# SFPGA.net
KiCad netlist of a schematic drawn in Altium Designer
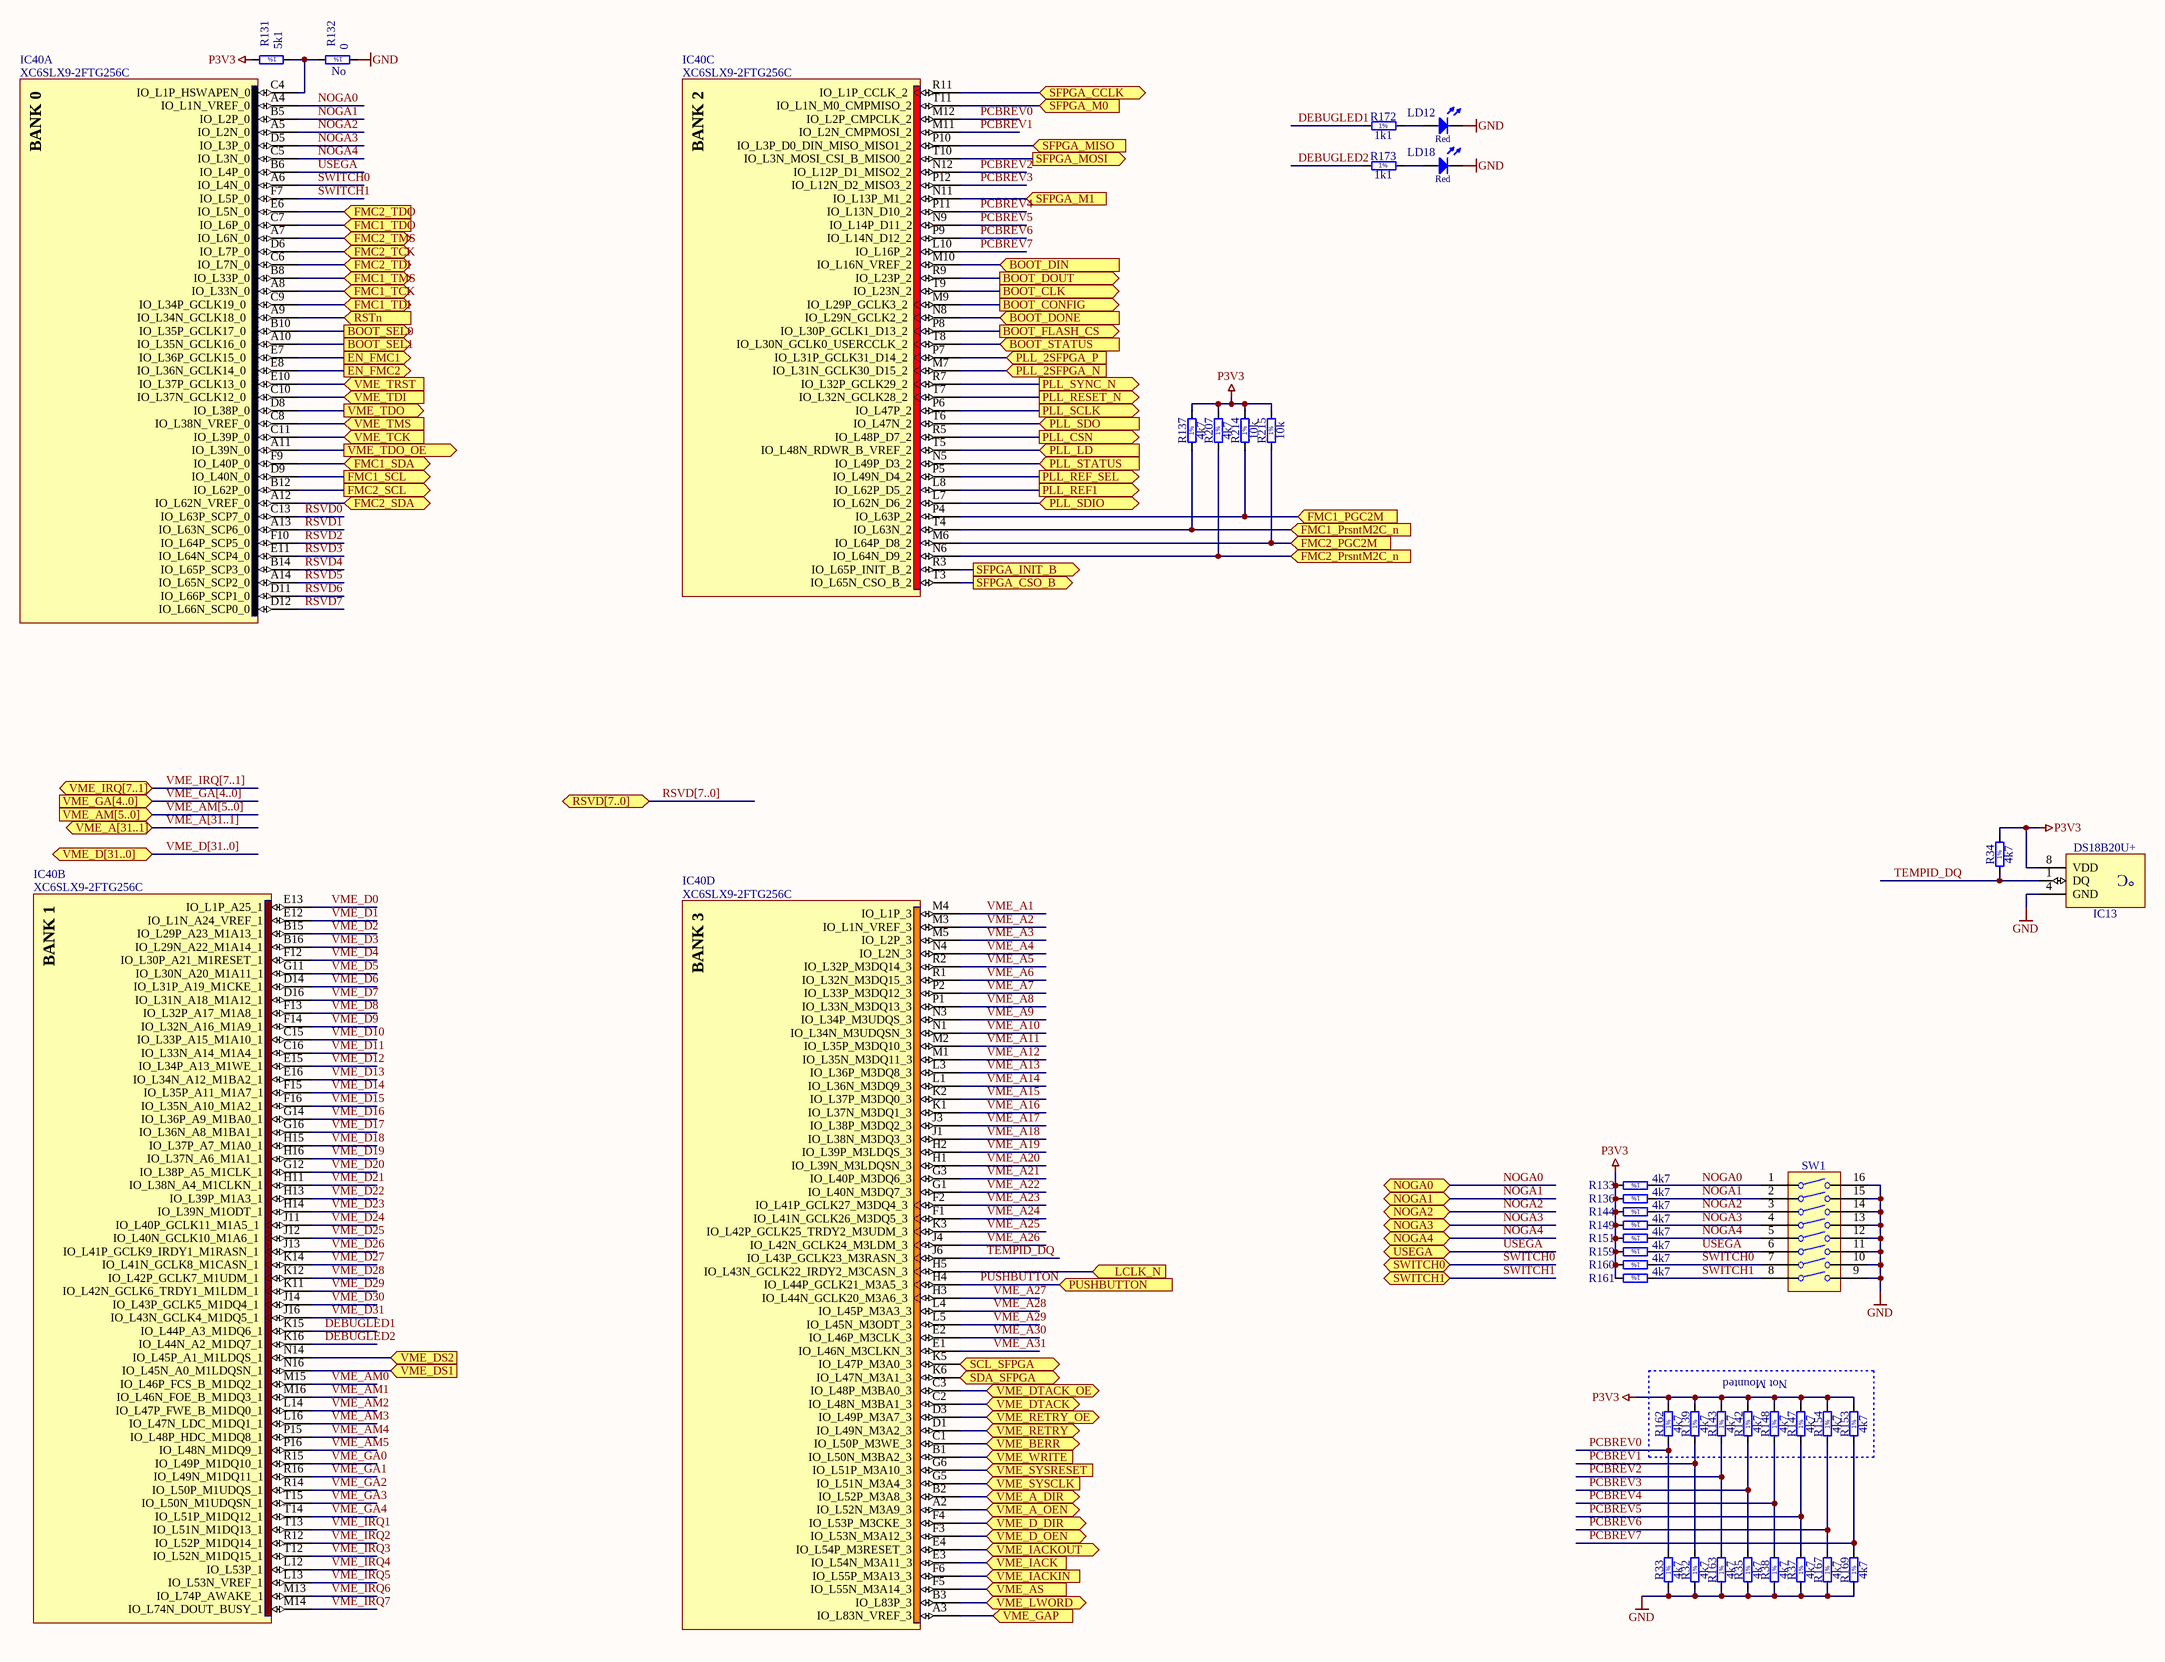
[diagram p0: SFPGA.SchDoc]

(export (version "E")
  (design (tool "Eeschema 10.0.6"))
  (components
    (comp (ref "IC13")
      (value "DS18B20U+")
      (footprint "SOP65P490X110-8N")
      (description "Programmable Resolution 1-Wire Digital Thermometer")
      (fields (field (name "MANUFACTURER") "DALLAS MAXIM") (field (name "AUTHOR") "CERN DEM JLC"))
      (libsource (lib "ICs And Semiconductors") (part "DS18B20U+"))
    )
    (comp (ref "IC40")
      (value "XC6SLX9-2FTG256C")
      (footprint "BGA256C100P16X16_1700X1700X155")
      (fields (field (name "MANUFACTURER") "XILINX") (field (name "AUTHOR") "CERN DEM JLC"))
      (libsource (lib "ICs And Semiconductors") (part "XC6SLX9-2FTG256C"))
    )
    (comp (ref "LD12")
      (value "Red")
      (footprint "LEDC1608X80N_RED")
      (description "LED Red 1C 2A")
      (fields
        (field (name "PART NUMBER") "LED_ROHM_SML-311UTT86K")
        (field (name "MANUFACTURER") "ROHM")
        (field (name "AUTHOR") "CERN DEM JLC")
      )
      (libsource (lib "ICs And Semiconductors") (part "LED Red 1C 2A"))
    )
    (comp (ref "LD18")
      (value "Red")
      (footprint "LEDC1608X80N_RED")
      (description "LED Red 1C 2A")
      (fields
        (field (name "PART NUMBER") "LED_ROHM_SML-311UTT86K")
        (field (name "MANUFACTURER") "ROHM")
        (field (name "AUTHOR") "CERN DEM JLC")
      )
      (libsource (lib "ICs And Semiconductors") (part "LED Red 1C 2A"))
    )
    (comp (ref "R32")
      (value "4k7")
      (footprint "RESC1608X55N")
      (description "Resistor - 1%")
      (fields
        (field (name "PART NUMBER") "R0603_4K7_1%_0.1W_100PPM")
        (field (name "POWER") "0.1W")
        (field (name "AUTHOR") "CERN DEM JLC")
      )
      (libsource (lib "Resistors") (part "Resistor - 1%"))
    )
    (comp (ref "R33")
      (value "4k7")
      (footprint "RESC1608X55N")
      (description "Resistor - 1%")
      (fields
        (field (name "PART NUMBER") "R0603_4K7_1%_0.1W_100PPM")
        (field (name "POWER") "0.1W")
        (field (name "AUTHOR") "CERN DEM JLC")
      )
      (libsource (lib "Resistors") (part "Resistor - 1%"))
    )
    (comp (ref "R34")
      (value "4k7")
      (footprint "RESC1608X55N")
      (description "Resistor - 1%")
      (fields
        (field (name "PART NUMBER") "R0603_4K7_1%_0.1W_100PPM")
        (field (name "POWER") "0.1W")
        (field (name "AUTHOR") "CERN DEM JLC")
      )
      (libsource (lib "Resistors") (part "Resistor - 1%"))
    )
    (comp (ref "R35")
      (value "4k7")
      (footprint "RESC1608X55N")
      (description "Resistor - 1%")
      (fields
        (field (name "PART NUMBER") "R0603_4K7_1%_0.1W_100PPM")
        (field (name "POWER") "0.1W")
        (field (name "AUTHOR") "CERN DEM JLC")
      )
      (libsource (lib "Resistors") (part "Resistor - 1%"))
    )
    (comp (ref "R37")
      (value "4k7")
      (footprint "RESC1608X55N")
      (description "Resistor - 1%")
      (fields
        (field (name "PART NUMBER") "R0603_4K7_1%_0.1W_100PPM")
        (field (name "POWER") "0.1W")
        (field (name "AUTHOR") "CERN DEM JLC")
      )
      (libsource (lib "Resistors") (part "Resistor - 1%"))
    )
    (comp (ref "R38")
      (value "4k7")
      (footprint "RESC1608X55N")
      (description "Resistor - 1%")
      (fields
        (field (name "PART NUMBER") "R0603_4K7_1%_0.1W_100PPM")
        (field (name "POWER") "0.1W")
        (field (name "AUTHOR") "CERN DEM JLC")
      )
      (libsource (lib "Resistors") (part "Resistor - 1%"))
    )
    (comp (ref "R131")
      (value "5k1")
      (footprint "RESC1608X55N")
      (description "Resistor - 1%")
      (fields
        (field (name "PART NUMBER") "R0603_5K1_1%_0.1W_100PPM")
        (field (name "POWER") "0.1W")
        (field (name "AUTHOR") "CERN DEM JLC")
      )
      (libsource (lib "Resistors") (part "Resistor - 1%"))
    )
    (comp (ref "R132")
      (value "0")
      (footprint "RESC1608X55N")
      (description "Resistor - 1%")
      (fields
        (field (name "PART NUMBER") "R0603_0R_JUMPER")
        (field (name "MANUFACTURER") "GENERIC")
        (field (name "MOUNTED") "No")
        (field (name "AUTHOR") "CERN DEM JLC")
      )
      (libsource (lib "Resistors") (part "Resistor - 1%"))
    )
    (comp (ref "R133")
      (value "4k7")
      (footprint "RESC1608X55N")
      (description "Resistor - 1%")
      (fields
        (field (name "PART NUMBER") "R0603_4K7_1%_0.1W_100PPM")
        (field (name "POWER") "0.1W")
        (field (name "AUTHOR") "CERN DEM JLC")
      )
      (libsource (lib "Resistors") (part "Resistor - 1%"))
    )
    (comp (ref "R136")
      (value "4k7")
      (footprint "RESC1608X55N")
      (description "Resistor - 1%")
      (fields
        (field (name "PART NUMBER") "R0603_4K7_1%_0.1W_100PPM")
        (field (name "POWER") "0.1W")
        (field (name "AUTHOR") "CERN DEM JLC")
      )
      (libsource (lib "Resistors") (part "Resistor - 1%"))
    )
    (comp (ref "R137")
      (value "4k7")
      (footprint "RESC1608X55N")
      (description "Resistor - 1%")
      (fields
        (field (name "PART NUMBER") "R0603_4K7_1%_0.1W_100PPM")
        (field (name "POWER") "0.1W")
        (field (name "AUTHOR") "CERN DEM JLC")
      )
      (libsource (lib "Resistors") (part "Resistor - 1%"))
    )
    (comp (ref "R139")
      (value "4k7")
      (footprint "RESC1608X55N")
      (description "Resistor - 1%")
      (fields
        (field (name "PART NUMBER") "R0603_4K7_1%_0.1W_100PPM")
        (field (name "POWER") "0.1W")
        (field (name "AUTHOR") "CERN DEM JLC")
      )
      (libsource (lib "Resistors") (part "Resistor - 1%"))
    )
    (comp (ref "R142")
      (value "4k7")
      (footprint "RESC1608X55N")
      (description "Resistor - 1%")
      (fields
        (field (name "PART NUMBER") "R0603_4K7_1%_0.1W_100PPM")
        (field (name "POWER") "0.1W")
        (field (name "AUTHOR") "CERN DEM JLC")
      )
      (libsource (lib "Resistors") (part "Resistor - 1%"))
    )
    (comp (ref "R143")
      (value "4k7")
      (footprint "RESC1608X55N")
      (description "Resistor - 1%")
      (fields
        (field (name "PART NUMBER") "R0603_4K7_1%_0.1W_100PPM")
        (field (name "POWER") "0.1W")
        (field (name "AUTHOR") "CERN DEM JLC")
      )
      (libsource (lib "Resistors") (part "Resistor - 1%"))
    )
    (comp (ref "R144")
      (value "4k7")
      (footprint "RESC1608X55N")
      (description "Resistor - 1%")
      (fields
        (field (name "PART NUMBER") "R0603_4K7_1%_0.1W_100PPM")
        (field (name "POWER") "0.1W")
        (field (name "AUTHOR") "CERN DEM JLC")
      )
      (libsource (lib "Resistors") (part "Resistor - 1%"))
    )
    (comp (ref "R147")
      (value "4k7")
      (footprint "RESC1608X55N")
      (description "Resistor - 1%")
      (fields
        (field (name "PART NUMBER") "R0603_4K7_1%_0.1W_100PPM")
        (field (name "POWER") "0.1W")
        (field (name "AUTHOR") "CERN DEM JLC")
      )
      (libsource (lib "Resistors") (part "Resistor - 1%"))
    )
    (comp (ref "R148")
      (value "4k7")
      (footprint "RESC1608X55N")
      (description "Resistor - 1%")
      (fields
        (field (name "PART NUMBER") "R0603_4K7_1%_0.1W_100PPM")
        (field (name "POWER") "0.1W")
        (field (name "AUTHOR") "CERN DEM JLC")
      )
      (libsource (lib "Resistors") (part "Resistor - 1%"))
    )
    (comp (ref "R149")
      (value "4k7")
      (footprint "RESC1608X55N")
      (description "Resistor - 1%")
      (fields
        (field (name "PART NUMBER") "R0603_4K7_1%_0.1W_100PPM")
        (field (name "POWER") "0.1W")
        (field (name "AUTHOR") "CERN DEM JLC")
      )
      (libsource (lib "Resistors") (part "Resistor - 1%"))
    )
    (comp (ref "R151")
      (value "4k7")
      (footprint "RESC1608X55N")
      (description "Resistor - 1%")
      (fields
        (field (name "PART NUMBER") "R0603_4K7_1%_0.1W_100PPM")
        (field (name "POWER") "0.1W")
        (field (name "AUTHOR") "CERN DEM JLC")
      )
      (libsource (lib "Resistors") (part "Resistor - 1%"))
    )
    (comp (ref "R153")
      (value "4k7")
      (footprint "RESC1608X55N")
      (description "Resistor - 1%")
      (fields
        (field (name "PART NUMBER") "R0603_4K7_1%_0.1W_100PPM")
        (field (name "POWER") "0.1W")
        (field (name "AUTHOR") "CERN DEM JLC")
      )
      (libsource (lib "Resistors") (part "Resistor - 1%"))
    )
    (comp (ref "R154")
      (value "4k7")
      (footprint "RESC1608X55N")
      (description "Resistor - 1%")
      (fields
        (field (name "PART NUMBER") "R0603_4K7_1%_0.1W_100PPM")
        (field (name "POWER") "0.1W")
        (field (name "AUTHOR") "CERN DEM JLC")
      )
      (libsource (lib "Resistors") (part "Resistor - 1%"))
    )
    (comp (ref "R159")
      (value "4k7")
      (footprint "RESC1608X55N")
      (description "Resistor - 1%")
      (fields
        (field (name "PART NUMBER") "R0603_4K7_1%_0.1W_100PPM")
        (field (name "POWER") "0.1W")
        (field (name "AUTHOR") "CERN DEM JLC")
      )
      (libsource (lib "Resistors") (part "Resistor - 1%"))
    )
    (comp (ref "R160")
      (value "4k7")
      (footprint "RESC1608X55N")
      (description "Resistor - 1%")
      (fields
        (field (name "PART NUMBER") "R0603_4K7_1%_0.1W_100PPM")
        (field (name "POWER") "0.1W")
        (field (name "AUTHOR") "CERN DEM JLC")
      )
      (libsource (lib "Resistors") (part "Resistor - 1%"))
    )
    (comp (ref "R161")
      (value "4k7")
      (footprint "RESC1608X55N")
      (description "Resistor - 1%")
      (fields
        (field (name "PART NUMBER") "R0603_4K7_1%_0.1W_100PPM")
        (field (name "POWER") "0.1W")
        (field (name "AUTHOR") "CERN DEM JLC")
      )
      (libsource (lib "Resistors") (part "Resistor - 1%"))
    )
    (comp (ref "R162")
      (value "4k7")
      (footprint "RESC1608X55N")
      (description "Resistor - 1%")
      (fields
        (field (name "PART NUMBER") "R0603_4K7_1%_0.1W_100PPM")
        (field (name "POWER") "0.1W")
        (field (name "AUTHOR") "CERN DEM JLC")
      )
      (libsource (lib "Resistors") (part "Resistor - 1%"))
    )
    (comp (ref "R163")
      (value "4k7")
      (footprint "RESC1608X55N")
      (description "Resistor - 1%")
      (fields
        (field (name "PART NUMBER") "R0603_4K7_1%_0.1W_100PPM")
        (field (name "POWER") "0.1W")
        (field (name "AUTHOR") "CERN DEM JLC")
      )
      (libsource (lib "Resistors") (part "Resistor - 1%"))
    )
    (comp (ref "R167")
      (value "4k7")
      (footprint "RESC1608X55N")
      (description "Resistor - 1%")
      (fields
        (field (name "PART NUMBER") "R0603_4K7_1%_0.1W_100PPM")
        (field (name "POWER") "0.1W")
        (field (name "AUTHOR") "CERN DEM JLC")
      )
      (libsource (lib "Resistors") (part "Resistor - 1%"))
    )
    (comp (ref "R169")
      (value "4k7")
      (footprint "RESC1608X55N")
      (description "Resistor - 1%")
      (fields
        (field (name "PART NUMBER") "R0603_4K7_1%_0.1W_100PPM")
        (field (name "POWER") "0.1W")
        (field (name "AUTHOR") "CERN DEM JLC")
      )
      (libsource (lib "Resistors") (part "Resistor - 1%"))
    )
    (comp (ref "R172")
      (value "1k1")
      (footprint "RESC1608X55N")
      (description "Resistor - 1%")
      (fields
        (field (name "PART NUMBER") "R0603_1K1_1%_0.1W_100PPM")
        (field (name "POWER") "0.1W")
        (field (name "AUTHOR") "CERN DEM JLC")
      )
      (libsource (lib "Resistors") (part "Resistor - 1%"))
    )
    (comp (ref "R173")
      (value "1k1")
      (footprint "RESC1608X55N")
      (description "Resistor - 1%")
      (fields
        (field (name "PART NUMBER") "R0603_1K1_1%_0.1W_100PPM")
        (field (name "POWER") "0.1W")
        (field (name "AUTHOR") "CERN DEM JLC")
      )
      (libsource (lib "Resistors") (part "Resistor - 1%"))
    )
    (comp (ref "R207")
      (value "4k7")
      (footprint "RESC1608X55N")
      (description "Resistor - 1%")
      (fields
        (field (name "PART NUMBER") "R0603_4K7_1%_0.1W_100PPM")
        (field (name "POWER") "0.1W")
        (field (name "AUTHOR") "CERN DEM JLC")
      )
      (libsource (lib "Resistors") (part "Resistor - 1%"))
    )
    (comp (ref "R214")
      (value "10k")
      (footprint "RESC1608X55N")
      (description "Resistor - 1%")
      (fields
        (field (name "PART NUMBER") "R0603_10K_1%_0.1W_100PPM")
        (field (name "POWER") "0.1W")
        (field (name "AUTHOR") "CERN DEM JLC")
      )
      (libsource (lib "Resistors") (part "Resistor - 1%"))
    )
    (comp (ref "R215")
      (value "10k")
      (footprint "RESC1608X55N")
      (description "Resistor - 1%")
      (fields
        (field (name "PART NUMBER") "R0603_10K_1%_0.1W_100PPM")
        (field (name "POWER") "0.1W")
        (field (name "AUTHOR") "CERN DEM JLC")
      )
      (libsource (lib "Resistors") (part "Resistor - 1%"))
    )
    (comp (ref "SW1")
      (value "Switch")
      (footprint "SW_TYCO_1-1571983-0")
      (description "8 Ways SPST DIP Switch")
      (fields
        (field (name "PART NUMBER") "SW_TYCO_1-1571983-0")
        (field (name "MANUFACTURER") "TYCO")
        (field (name "AUTHOR") "CERN DEM JLC")
      )
      (libsource (lib "Eletro-mechanical") (part "SW 8x SPST DIP Switch"))
    )
  )
  (nets
    (net (code "1") (name "/BOOT_CLK") (class "Default")
      (node (ref "IC40") (pin "T9") (pinfunction "IO_L23N_2_T9") (pintype "bidirectional"))
    )
    (net (code "2") (name "/BOOT_CONFIG") (class "Default")
      (node (ref "IC40") (pin "M9") (pinfunction "IO_L29P_GCLK3_2_M9") (pintype "bidirectional"))
    )
    (net (code "3") (name "/BOOT_DIN") (class "Default")
      (node (ref "IC40") (pin "M10") (pinfunction "IO_L16N_VREF_2_M10") (pintype "bidirectional"))
    )
    (net (code "4") (name "/BOOT_DONE") (class "Default")
      (node (ref "IC40") (pin "N8") (pinfunction "IO_L29N_GCLK2_2_N8") (pintype "bidirectional"))
    )
    (net (code "5") (name "/BOOT_DOUT") (class "Default")
      (node (ref "IC40") (pin "R9") (pinfunction "IO_L23P_2_R9") (pintype "bidirectional"))
    )
    (net (code "6") (name "/BOOT_FLASH_CS") (class "Default")
      (node (ref "IC40") (pin "P8") (pinfunction "IO_L30P_GCLK1_D13_2_P8") (pintype "bidirectional"))
    )
    (net (code "7") (name "/BOOT_SEL0") (class "Default")
      (node (ref "IC40") (pin "B10") (pinfunction "IO_L35P_GCLK17_0_B10") (pintype "bidirectional"))
    )
    (net (code "8") (name "/BOOT_SEL1") (class "Default")
      (node (ref "IC40") (pin "A10") (pinfunction "IO_L35N_GCLK16_0_A10") (pintype "bidirectional"))
    )
    (net (code "9") (name "/BOOT_STATUS") (class "Default")
      (node (ref "IC40") (pin "T8") (pinfunction "IO_L30N_GCLK0_USERCCLK_2_T8") (pintype "bidirectional"))
    )
    (net (code "10") (name "/DEBUGLED1") (class "Default")
      (node (ref "IC40") (pin "K15") (pinfunction "IO_L44P_A3_M1DQ6_1_K15") (pintype "bidirectional"))
      (node (ref "R172") (pin "1") (pinfunction "1_1") (pintype "passive"))
    )
    (net (code "11") (name "/DEBUGLED2") (class "Default")
      (node (ref "IC40") (pin "K16") (pinfunction "IO_L44N_A2_M1DQ7_1_K16") (pintype "bidirectional"))
      (node (ref "R173") (pin "1") (pinfunction "1_1") (pintype "passive"))
    )
    (net (code "12") (name "/EN_FMC1") (class "Default")
      (node (ref "IC40") (pin "E7") (pinfunction "IO_L36P_GCLK15_0_E7") (pintype "bidirectional"))
    )
    (net (code "13") (name "/EN_FMC2") (class "Default")
      (node (ref "IC40") (pin "E8") (pinfunction "IO_L36N_GCLK14_0_E8") (pintype "bidirectional"))
    )
    (net (code "14") (name "/FMC1_PGC2M") (class "Default")
      (node (ref "IC40") (pin "P4") (pinfunction "IO_L63P_2_P4") (pintype "bidirectional"))
      (node (ref "R214") (pin "1") (pinfunction "1_1") (pintype "passive"))
    )
    (net (code "15") (name "/FMC1_PrsntM2C_n") (class "Default")
      (node (ref "IC40") (pin "T4") (pinfunction "IO_L63N_2_T4") (pintype "bidirectional"))
      (node (ref "R137") (pin "1") (pinfunction "1_1") (pintype "passive"))
    )
    (net (code "16") (name "/FMC1_SCL") (class "Default")
      (node (ref "IC40") (pin "D9") (pinfunction "IO_L40N_0_D9") (pintype "bidirectional"))
    )
    (net (code "17") (name "/FMC1_SDA") (class "Default")
      (node (ref "IC40") (pin "F9") (pinfunction "IO_L40P_0_F9") (pintype "bidirectional"))
    )
    (net (code "18") (name "/FMC1_TCK") (class "Default")
      (node (ref "IC40") (pin "A8") (pinfunction "IO_L33N_0_A8") (pintype "bidirectional"))
    )
    (net (code "19") (name "/FMC1_TDI") (class "Default")
      (node (ref "IC40") (pin "C9") (pinfunction "IO_L34P_GCLK19_0_C9") (pintype "bidirectional"))
    )
    (net (code "20") (name "/FMC1_TDO") (class "Default")
      (node (ref "IC40") (pin "C7") (pinfunction "IO_L6P_0_C7") (pintype "bidirectional"))
    )
    (net (code "21") (name "/FMC1_TMS") (class "Default")
      (node (ref "IC40") (pin "B8") (pinfunction "IO_L33P_0_B8") (pintype "bidirectional"))
    )
    (net (code "22") (name "/FMC2_PGC2M") (class "Default")
      (node (ref "IC40") (pin "M6") (pinfunction "IO_L64P_D8_2_M6") (pintype "bidirectional"))
      (node (ref "R215") (pin "1") (pinfunction "1_1") (pintype "passive"))
    )
    (net (code "23") (name "/FMC2_PrsntM2C_n") (class "Default")
      (node (ref "IC40") (pin "N6") (pinfunction "IO_L64N_D9_2_N6") (pintype "bidirectional"))
      (node (ref "R207") (pin "1") (pinfunction "1_1") (pintype "passive"))
    )
    (net (code "24") (name "/FMC2_SCL") (class "Default")
      (node (ref "IC40") (pin "B12") (pinfunction "IO_L62P_0_B12") (pintype "bidirectional"))
    )
    (net (code "25") (name "/FMC2_SDA") (class "Default")
      (node (ref "IC40") (pin "A12") (pinfunction "IO_L62N_VREF_0_A12") (pintype "bidirectional"))
    )
    (net (code "26") (name "/FMC2_TCK") (class "Default")
      (node (ref "IC40") (pin "D6") (pinfunction "IO_L7P_0_D6") (pintype "bidirectional"))
    )
    (net (code "27") (name "/FMC2_TDI") (class "Default")
      (node (ref "IC40") (pin "C6") (pinfunction "IO_L7N_0_C6") (pintype "bidirectional"))
    )
    (net (code "28") (name "/FMC2_TDO") (class "Default")
      (node (ref "IC40") (pin "E6") (pinfunction "IO_L5N_0_E6") (pintype "bidirectional"))
    )
    (net (code "29") (name "/FMC2_TMS") (class "Default")
      (node (ref "IC40") (pin "A7") (pinfunction "IO_L6N_0_A7") (pintype "bidirectional"))
    )
    (net (code "30") (name "/LCLK_N") (class "Default")
      (node (ref "IC40") (pin "H5") (pinfunction "IO_L43N_GCLK22_IRDY2_M3CASN_3_H5") (pintype "bidirectional"))
    )
    (net (code "31") (name "/NOGA0") (class "Default")
      (node (ref "IC40") (pin "A4") (pinfunction "IO_L1N_VREF_0_A4") (pintype "bidirectional"))
      (node (ref "R133") (pin "1") (pinfunction "1_1") (pintype "passive"))
      (node (ref "SW1") (pin "1") (pinfunction "1_1") (pintype "passive"))
    )
    (net (code "32") (name "/NOGA1") (class "Default")
      (node (ref "IC40") (pin "B5") (pinfunction "IO_L2P_0_B5") (pintype "bidirectional"))
      (node (ref "R136") (pin "1") (pinfunction "1_1") (pintype "passive"))
      (node (ref "SW1") (pin "2") (pinfunction "2_2") (pintype "passive"))
    )
    (net (code "33") (name "/NOGA2") (class "Default")
      (node (ref "IC40") (pin "A5") (pinfunction "IO_L2N_0_A5") (pintype "bidirectional"))
      (node (ref "R144") (pin "1") (pinfunction "1_1") (pintype "passive"))
      (node (ref "SW1") (pin "3") (pinfunction "3_3") (pintype "passive"))
    )
    (net (code "34") (name "/NOGA3") (class "Default")
      (node (ref "IC40") (pin "D5") (pinfunction "IO_L3P_0_D5") (pintype "bidirectional"))
      (node (ref "R149") (pin "1") (pinfunction "1_1") (pintype "passive"))
      (node (ref "SW1") (pin "4") (pinfunction "4_4") (pintype "passive"))
    )
    (net (code "35") (name "/NOGA4") (class "Default")
      (node (ref "IC40") (pin "C5") (pinfunction "IO_L3N_0_C5") (pintype "bidirectional"))
      (node (ref "R151") (pin "1") (pinfunction "1_1") (pintype "passive"))
      (node (ref "SW1") (pin "5") (pinfunction "5_5") (pintype "passive"))
    )
    (net (code "36") (name "/PCBREV0") (class "Default")
      (node (ref "IC40") (pin "M12") (pinfunction "IO_L2P_CMPCLK_2_M12") (pintype "bidirectional"))
      (node (ref "R162") (pin "1") (pinfunction "1_1") (pintype "passive"))
      (node (ref "R33") (pin "2") (pinfunction "2_2") (pintype "passive"))
    )
    (net (code "37") (name "/PCBREV1") (class "Default")
      (node (ref "IC40") (pin "M11") (pinfunction "IO_L2N_CMPMOSI_2_M11") (pintype "bidirectional"))
      (node (ref "R139") (pin "1") (pinfunction "1_1") (pintype "passive"))
      (node (ref "R32") (pin "2") (pinfunction "2_2") (pintype "passive"))
    )
    (net (code "38") (name "/PCBREV2") (class "Default")
      (node (ref "IC40") (pin "N12") (pinfunction "IO_L12P_D1_MISO2_2_N12") (pintype "bidirectional"))
      (node (ref "R143") (pin "1") (pinfunction "1_1") (pintype "passive"))
      (node (ref "R163") (pin "2") (pinfunction "2_2") (pintype "passive"))
    )
    (net (code "39") (name "/PCBREV3") (class "Default")
      (node (ref "IC40") (pin "P12") (pinfunction "IO_L12N_D2_MISO3_2_P12") (pintype "bidirectional"))
      (node (ref "R142") (pin "1") (pinfunction "1_1") (pintype "passive"))
      (node (ref "R35") (pin "2") (pinfunction "2_2") (pintype "passive"))
    )
    (net (code "40") (name "/PCBREV4") (class "Default")
      (node (ref "IC40") (pin "P11") (pinfunction "IO_L13N_D10_2_P11") (pintype "bidirectional"))
      (node (ref "R148") (pin "1") (pinfunction "1_1") (pintype "passive"))
      (node (ref "R38") (pin "2") (pinfunction "2_2") (pintype "passive"))
    )
    (net (code "41") (name "/PCBREV5") (class "Default")
      (node (ref "IC40") (pin "N9") (pinfunction "IO_L14P_D11_2_N9") (pintype "bidirectional"))
      (node (ref "R147") (pin "1") (pinfunction "1_1") (pintype "passive"))
      (node (ref "R37") (pin "2") (pinfunction "2_2") (pintype "passive"))
    )
    (net (code "42") (name "/PCBREV6") (class "Default")
      (node (ref "IC40") (pin "P9") (pinfunction "IO_L14N_D12_2_P9") (pintype "bidirectional"))
      (node (ref "R154") (pin "1") (pinfunction "1_1") (pintype "passive"))
      (node (ref "R167") (pin "2") (pinfunction "2_2") (pintype "passive"))
    )
    (net (code "43") (name "/PCBREV7") (class "Default")
      (node (ref "IC40") (pin "L10") (pinfunction "IO_L16P_2_L10") (pintype "bidirectional"))
      (node (ref "R153") (pin "1") (pinfunction "1_1") (pintype "passive"))
      (node (ref "R169") (pin "2") (pinfunction "2_2") (pintype "passive"))
    )
    (net (code "44") (name "/PLL_2SFPGA_N") (class "Default")
      (node (ref "IC40") (pin "M7") (pinfunction "IO_L31N_GCLK30_D15_2_M7") (pintype "bidirectional"))
    )
    (net (code "45") (name "/PLL_2SFPGA_P") (class "Default")
      (node (ref "IC40") (pin "P7") (pinfunction "IO_L31P_GCLK31_D14_2_P7") (pintype "bidirectional"))
    )
    (net (code "46") (name "/PLL_CSN") (class "Default")
      (node (ref "IC40") (pin "R5") (pinfunction "IO_L48P_D7_2_R5") (pintype "bidirectional"))
    )
    (net (code "47") (name "/PLL_LD") (class "Default")
      (node (ref "IC40") (pin "T5") (pinfunction "IO_L48N_RDWR_B_VREF_2_T5") (pintype "bidirectional"))
    )
    (net (code "48") (name "/PLL_REF1") (class "Default")
      (node (ref "IC40") (pin "L8") (pinfunction "IO_L62P_D5_2_L8") (pintype "bidirectional"))
    )
    (net (code "49") (name "/PLL_REF_SEL") (class "Default")
      (node (ref "IC40") (pin "P5") (pinfunction "IO_L49N_D4_2_P5") (pintype "bidirectional"))
    )
    (net (code "50") (name "/PLL_RESET_N") (class "Default")
      (node (ref "IC40") (pin "T7") (pinfunction "IO_L32N_GCLK28_2_T7") (pintype "bidirectional"))
    )
    (net (code "51") (name "/PLL_SCLK") (class "Default")
      (node (ref "IC40") (pin "P6") (pinfunction "IO_L47P_2_P6") (pintype "bidirectional"))
    )
    (net (code "52") (name "/PLL_SDIO") (class "Default")
      (node (ref "IC40") (pin "L7") (pinfunction "IO_L62N_D6_2_L7") (pintype "bidirectional"))
    )
    (net (code "53") (name "/PLL_SDO") (class "Default")
      (node (ref "IC40") (pin "T6") (pinfunction "IO_L47N_2_T6") (pintype "bidirectional"))
    )
    (net (code "54") (name "/PLL_STATUS") (class "Default")
      (node (ref "IC40") (pin "N5") (pinfunction "IO_L49P_D3_2_N5") (pintype "bidirectional"))
    )
    (net (code "55") (name "/PLL_SYNC_N") (class "Default")
      (node (ref "IC40") (pin "R7") (pinfunction "IO_L32P_GCLK29_2_R7") (pintype "bidirectional"))
    )
    (net (code "56") (name "/PUSHBUTTON") (class "Default")
      (node (ref "IC40") (pin "H4") (pinfunction "IO_L44P_GCLK21_M3A5_3_H4") (pintype "bidirectional"))
    )
    (net (code "57") (name "/RSTn") (class "Default")
      (node (ref "IC40") (pin "A9") (pinfunction "IO_L34N_GCLK18_0_A9") (pintype "bidirectional"))
    )
    (net (code "58") (name "/RSVD0") (class "Default")
      (node (ref "IC40") (pin "C13") (pinfunction "IO_L63P_SCP7_0_C13") (pintype "bidirectional"))
    )
    (net (code "59") (name "/RSVD1") (class "Default")
      (node (ref "IC40") (pin "A13") (pinfunction "IO_L63N_SCP6_0_A13") (pintype "bidirectional"))
    )
    (net (code "60") (name "/RSVD2") (class "Default")
      (node (ref "IC40") (pin "F10") (pinfunction "IO_L64P_SCP5_0_F10") (pintype "bidirectional"))
    )
    (net (code "61") (name "/RSVD3") (class "Default")
      (node (ref "IC40") (pin "E11") (pinfunction "IO_L64N_SCP4_0_E11") (pintype "bidirectional"))
    )
    (net (code "62") (name "/RSVD4") (class "Default")
      (node (ref "IC40") (pin "B14") (pinfunction "IO_L65P_SCP3_0_B14") (pintype "bidirectional"))
    )
    (net (code "63") (name "/RSVD5") (class "Default")
      (node (ref "IC40") (pin "A14") (pinfunction "IO_L65N_SCP2_0_A14") (pintype "bidirectional"))
    )
    (net (code "64") (name "/RSVD6") (class "Default")
      (node (ref "IC40") (pin "D11") (pinfunction "IO_L66P_SCP1_0_D11") (pintype "bidirectional"))
    )
    (net (code "65") (name "/RSVD7") (class "Default")
      (node (ref "IC40") (pin "D12") (pinfunction "IO_L66N_SCP0_0_D12") (pintype "bidirectional"))
    )
    (net (code "67") (name "/SCL_SFPGA") (class "Default")
      (node (ref "IC40") (pin "K5") (pinfunction "IO_L47P_M3A0_3_K5") (pintype "bidirectional"))
    )
    (net (code "68") (name "/SDA_SFPGA") (class "Default")
      (node (ref "IC40") (pin "K6") (pinfunction "IO_L47N_M3A1_3_K6") (pintype "bidirectional"))
    )
    (net (code "69") (name "/SFPGA_CCLK") (class "Default")
      (node (ref "IC40") (pin "R11") (pinfunction "IO_L1P_CCLK_2_R11") (pintype "bidirectional"))
    )
    (net (code "70") (name "/SFPGA_CSO_B") (class "Default")
      (node (ref "IC40") (pin "T3") (pinfunction "IO_L65N_CSO_B_2_T3") (pintype "bidirectional"))
    )
    (net (code "71") (name "/SFPGA_INIT_B") (class "Default")
      (node (ref "IC40") (pin "R3") (pinfunction "IO_L65P_INIT_B_2_R3") (pintype "bidirectional"))
    )
    (net (code "72") (name "/SFPGA_M0") (class "Default")
      (node (ref "IC40") (pin "T11") (pinfunction "IO_L1N_M0_CMPMISO_2_T11") (pintype "bidirectional"))
    )
    (net (code "73") (name "/SFPGA_M1") (class "Default")
      (node (ref "IC40") (pin "N11") (pinfunction "IO_L13P_M1_2_N11") (pintype "bidirectional"))
    )
    (net (code "74") (name "/SFPGA_MISO") (class "Default")
      (node (ref "IC40") (pin "P10") (pinfunction "IO_L3P_D0_DIN_MISO_MISO1_2_P10") (pintype "bidirectional"))
    )
    (net (code "75") (name "/SFPGA_MOSI") (class "Default")
      (node (ref "IC40") (pin "T10") (pinfunction "IO_L3N_MOSI_CSI_B_MISO0_2_T10") (pintype "bidirectional"))
    )
    (net (code "76") (name "/SWITCH0") (class "Default")
      (node (ref "IC40") (pin "A6") (pinfunction "IO_L4N_0_A6") (pintype "bidirectional"))
      (node (ref "R160") (pin "1") (pinfunction "1_1") (pintype "passive"))
      (node (ref "SW1") (pin "7") (pinfunction "7_7") (pintype "passive"))
    )
    (net (code "77") (name "/SWITCH1") (class "Default")
      (node (ref "IC40") (pin "F7") (pinfunction "IO_L5P_0_F7") (pintype "bidirectional"))
      (node (ref "R161") (pin "1") (pinfunction "1_1") (pintype "passive"))
      (node (ref "SW1") (pin "8") (pinfunction "8_8") (pintype "passive"))
    )
    (net (code "78") (name "/TEMPID_DQ") (class "Default")
      (node (ref "IC13") (pin "1") (pinfunction "DQ_1") (pintype "bidirectional"))
      (node (ref "IC40") (pin "J6") (pinfunction "IO_L43P_GCLK23_M3RASN_3_J6") (pintype "bidirectional"))
      (node (ref "R34") (pin "1") (pinfunction "1_1") (pintype "passive"))
    )
    (net (code "79") (name "/USEGA") (class "Default")
      (node (ref "IC40") (pin "B6") (pinfunction "IO_L4P_0_B6") (pintype "bidirectional"))
      (node (ref "R159") (pin "1") (pinfunction "1_1") (pintype "passive"))
      (node (ref "SW1") (pin "6") (pinfunction "6_6") (pintype "passive"))
    )
    (net (code "80") (name "/VME_A1") (class "Default")
      (node (ref "IC40") (pin "M4") (pinfunction "IO_L1P_3_M4") (pintype "bidirectional"))
    )
    (net (code "81") (name "/VME_A2") (class "Default")
      (node (ref "IC40") (pin "M3") (pinfunction "IO_L1N_VREF_3_M3") (pintype "bidirectional"))
    )
    (net (code "82") (name "/VME_A3") (class "Default")
      (node (ref "IC40") (pin "M5") (pinfunction "IO_L2P_3_M5") (pintype "bidirectional"))
    )
    (net (code "83") (name "/VME_A4") (class "Default")
      (node (ref "IC40") (pin "N4") (pinfunction "IO_L2N_3_N4") (pintype "bidirectional"))
    )
    (net (code "84") (name "/VME_A5") (class "Default")
      (node (ref "IC40") (pin "R2") (pinfunction "IO_L32P_M3DQ14_3_R2") (pintype "bidirectional"))
    )
    (net (code "85") (name "/VME_A6") (class "Default")
      (node (ref "IC40") (pin "R1") (pinfunction "IO_L32N_M3DQ15_3_R1") (pintype "bidirectional"))
    )
    (net (code "86") (name "/VME_A7") (class "Default")
      (node (ref "IC40") (pin "P2") (pinfunction "IO_L33P_M3DQ12_3_P2") (pintype "bidirectional"))
    )
    (net (code "87") (name "/VME_A8") (class "Default")
      (node (ref "IC40") (pin "P1") (pinfunction "IO_L33N_M3DQ13_3_P1") (pintype "bidirectional"))
    )
    (net (code "88") (name "/VME_A9") (class "Default")
      (node (ref "IC40") (pin "N3") (pinfunction "IO_L34P_M3UDQS_3_N3") (pintype "bidirectional"))
    )
    (net (code "89") (name "/VME_A10") (class "Default")
      (node (ref "IC40") (pin "N1") (pinfunction "IO_L34N_M3UDQSN_3_N1") (pintype "bidirectional"))
    )
    (net (code "90") (name "/VME_A11") (class "Default")
      (node (ref "IC40") (pin "M2") (pinfunction "IO_L35P_M3DQ10_3_M2") (pintype "bidirectional"))
    )
    (net (code "91") (name "/VME_A12") (class "Default")
      (node (ref "IC40") (pin "M1") (pinfunction "IO_L35N_M3DQ11_3_M1") (pintype "bidirectional"))
    )
    (net (code "92") (name "/VME_A13") (class "Default")
      (node (ref "IC40") (pin "L3") (pinfunction "IO_L36P_M3DQ8_3_L3") (pintype "bidirectional"))
    )
    (net (code "93") (name "/VME_A14") (class "Default")
      (node (ref "IC40") (pin "L1") (pinfunction "IO_L36N_M3DQ9_3_L1") (pintype "bidirectional"))
    )
    (net (code "94") (name "/VME_A15") (class "Default")
      (node (ref "IC40") (pin "K2") (pinfunction "IO_L37P_M3DQ0_3_K2") (pintype "bidirectional"))
    )
    (net (code "95") (name "/VME_A16") (class "Default")
      (node (ref "IC40") (pin "K1") (pinfunction "IO_L37N_M3DQ1_3_K1") (pintype "bidirectional"))
    )
    (net (code "96") (name "/VME_A17") (class "Default")
      (node (ref "IC40") (pin "J3") (pinfunction "IO_L38P_M3DQ2_3_J3") (pintype "bidirectional"))
    )
    (net (code "97") (name "/VME_A18") (class "Default")
      (node (ref "IC40") (pin "J1") (pinfunction "IO_L38N_M3DQ3_3_J1") (pintype "bidirectional"))
    )
    (net (code "98") (name "/VME_A19") (class "Default")
      (node (ref "IC40") (pin "H2") (pinfunction "IO_L39P_M3LDQS_3_H2") (pintype "bidirectional"))
    )
    (net (code "99") (name "/VME_A20") (class "Default")
      (node (ref "IC40") (pin "H1") (pinfunction "IO_L39N_M3LDQSN_3_H1") (pintype "bidirectional"))
    )
    (net (code "100") (name "/VME_A21") (class "Default")
      (node (ref "IC40") (pin "G3") (pinfunction "IO_L40P_M3DQ6_3_G3") (pintype "bidirectional"))
    )
    (net (code "101") (name "/VME_A22") (class "Default")
      (node (ref "IC40") (pin "G1") (pinfunction "IO_L40N_M3DQ7_3_G1") (pintype "bidirectional"))
    )
    (net (code "102") (name "/VME_A23") (class "Default")
      (node (ref "IC40") (pin "F2") (pinfunction "IO_L41P_GCLK27_M3DQ4_3_F2") (pintype "bidirectional"))
    )
    (net (code "103") (name "/VME_A24") (class "Default")
      (node (ref "IC40") (pin "F1") (pinfunction "IO_L41N_GCLK26_M3DQ5_3_F1") (pintype "bidirectional"))
    )
    (net (code "104") (name "/VME_A25") (class "Default")
      (node (ref "IC40") (pin "K3") (pinfunction "IO_L42P_GCLK25_TRDY2_M3UDM_3_K3") (pintype "bidirectional"))
    )
    (net (code "105") (name "/VME_A26") (class "Default")
      (node (ref "IC40") (pin "J4") (pinfunction "IO_L42N_GCLK24_M3LDM_3_J4") (pintype "bidirectional"))
    )
    (net (code "106") (name "/VME_A27") (class "Default")
      (node (ref "IC40") (pin "H3") (pinfunction "IO_L44N_GCLK20_M3A6_3_H3") (pintype "bidirectional"))
    )
    (net (code "107") (name "/VME_A28") (class "Default")
      (node (ref "IC40") (pin "L4") (pinfunction "IO_L45P_M3A3_3_L4") (pintype "bidirectional"))
    )
    (net (code "108") (name "/VME_A29") (class "Default")
      (node (ref "IC40") (pin "L5") (pinfunction "IO_L45N_M3ODT_3_L5") (pintype "bidirectional"))
    )
    (net (code "109") (name "/VME_A30") (class "Default")
      (node (ref "IC40") (pin "E2") (pinfunction "IO_L46P_M3CLK_3_E2") (pintype "bidirectional"))
    )
    (net (code "110") (name "/VME_A31") (class "Default")
      (node (ref "IC40") (pin "E1") (pinfunction "IO_L46N_M3CLKN_3_E1") (pintype "bidirectional"))
    )
    (net (code "111") (name "/VME_AM0") (class "Default")
      (node (ref "IC40") (pin "M15") (pinfunction "IO_L46P_FCS_B_M1DQ2_1_M15") (pintype "bidirectional"))
    )
    (net (code "112") (name "/VME_AM1") (class "Default")
      (node (ref "IC40") (pin "M16") (pinfunction "IO_L46N_FOE_B_M1DQ3_1_M16") (pintype "bidirectional"))
    )
    (net (code "113") (name "/VME_AM2") (class "Default")
      (node (ref "IC40") (pin "L14") (pinfunction "IO_L47P_FWE_B_M1DQ0_1_L14") (pintype "bidirectional"))
    )
    (net (code "114") (name "/VME_AM3") (class "Default")
      (node (ref "IC40") (pin "L16") (pinfunction "IO_L47N_LDC_M1DQ1_1_L16") (pintype "bidirectional"))
    )
    (net (code "115") (name "/VME_AM4") (class "Default")
      (node (ref "IC40") (pin "P15") (pinfunction "IO_L48P_HDC_M1DQ8_1_P15") (pintype "bidirectional"))
    )
    (net (code "116") (name "/VME_AM5") (class "Default")
      (node (ref "IC40") (pin "P16") (pinfunction "IO_L48N_M1DQ9_1_P16") (pintype "bidirectional"))
    )
    (net (code "118") (name "/VME_AS") (class "Default")
      (node (ref "IC40") (pin "F5") (pinfunction "IO_L55N_M3A14_3_F5") (pintype "bidirectional"))
    )
    (net (code "120") (name "/VME_A_DIR") (class "Default")
      (node (ref "IC40") (pin "B2") (pinfunction "IO_L52P_M3A8_3_B2") (pintype "bidirectional"))
    )
    (net (code "121") (name "/VME_A_OEN") (class "Default")
      (node (ref "IC40") (pin "A2") (pinfunction "IO_L52N_M3A9_3_A2") (pintype "bidirectional"))
    )
    (net (code "122") (name "/VME_BERR") (class "Default")
      (node (ref "IC40") (pin "C1") (pinfunction "IO_L50P_M3WE_3_C1") (pintype "bidirectional"))
    )
    (net (code "123") (name "/VME_D0") (class "Default")
      (node (ref "IC40") (pin "E13") (pinfunction "IO_L1P_A25_1_E13") (pintype "bidirectional"))
    )
    (net (code "124") (name "/VME_D1") (class "Default")
      (node (ref "IC40") (pin "E12") (pinfunction "IO_L1N_A24_VREF_1_E12") (pintype "bidirectional"))
    )
    (net (code "125") (name "/VME_D2") (class "Default")
      (node (ref "IC40") (pin "B15") (pinfunction "IO_L29P_A23_M1A13_1_B15") (pintype "bidirectional"))
    )
    (net (code "126") (name "/VME_D3") (class "Default")
      (node (ref "IC40") (pin "B16") (pinfunction "IO_L29N_A22_M1A14_1_B16") (pintype "bidirectional"))
    )
    (net (code "127") (name "/VME_D4") (class "Default")
      (node (ref "IC40") (pin "F12") (pinfunction "IO_L30P_A21_M1RESET_1_F12") (pintype "bidirectional"))
    )
    (net (code "128") (name "/VME_D5") (class "Default")
      (node (ref "IC40") (pin "G11") (pinfunction "IO_L30N_A20_M1A11_1_G11") (pintype "bidirectional"))
    )
    (net (code "129") (name "/VME_D6") (class "Default")
      (node (ref "IC40") (pin "D14") (pinfunction "IO_L31P_A19_M1CKE_1_D14") (pintype "bidirectional"))
    )
    (net (code "130") (name "/VME_D7") (class "Default")
      (node (ref "IC40") (pin "D16") (pinfunction "IO_L31N_A18_M1A12_1_D16") (pintype "bidirectional"))
    )
    (net (code "131") (name "/VME_D8") (class "Default")
      (node (ref "IC40") (pin "F13") (pinfunction "IO_L32P_A17_M1A8_1_F13") (pintype "bidirectional"))
    )
    (net (code "132") (name "/VME_D9") (class "Default")
      (node (ref "IC40") (pin "F14") (pinfunction "IO_L32N_A16_M1A9_1_F14") (pintype "bidirectional"))
    )
    (net (code "133") (name "/VME_D10") (class "Default")
      (node (ref "IC40") (pin "C15") (pinfunction "IO_L33P_A15_M1A10_1_C15") (pintype "bidirectional"))
    )
    (net (code "134") (name "/VME_D11") (class "Default")
      (node (ref "IC40") (pin "C16") (pinfunction "IO_L33N_A14_M1A4_1_C16") (pintype "bidirectional"))
    )
    (net (code "135") (name "/VME_D12") (class "Default")
      (node (ref "IC40") (pin "E15") (pinfunction "IO_L34P_A13_M1WE_1_E15") (pintype "bidirectional"))
    )
    (net (code "136") (name "/VME_D13") (class "Default")
      (node (ref "IC40") (pin "E16") (pinfunction "IO_L34N_A12_M1BA2_1_E16") (pintype "bidirectional"))
    )
    (net (code "137") (name "/VME_D14") (class "Default")
      (node (ref "IC40") (pin "F15") (pinfunction "IO_L35P_A11_M1A7_1_F15") (pintype "bidirectional"))
    )
    (net (code "138") (name "/VME_D15") (class "Default")
      (node (ref "IC40") (pin "F16") (pinfunction "IO_L35N_A10_M1A2_1_F16") (pintype "bidirectional"))
    )
    (net (code "139") (name "/VME_D16") (class "Default")
      (node (ref "IC40") (pin "G14") (pinfunction "IO_L36P_A9_M1BA0_1_G14") (pintype "bidirectional"))
    )
    (net (code "140") (name "/VME_D17") (class "Default")
      (node (ref "IC40") (pin "G16") (pinfunction "IO_L36N_A8_M1BA1_1_G16") (pintype "bidirectional"))
    )
    (net (code "141") (name "/VME_D18") (class "Default")
      (node (ref "IC40") (pin "H15") (pinfunction "IO_L37P_A7_M1A0_1_H15") (pintype "bidirectional"))
    )
    (net (code "142") (name "/VME_D19") (class "Default")
      (node (ref "IC40") (pin "H16") (pinfunction "IO_L37N_A6_M1A1_1_H16") (pintype "bidirectional"))
    )
    (net (code "143") (name "/VME_D20") (class "Default")
      (node (ref "IC40") (pin "G12") (pinfunction "IO_L38P_A5_M1CLK_1_G12") (pintype "bidirectional"))
    )
    (net (code "144") (name "/VME_D21") (class "Default")
      (node (ref "IC40") (pin "H11") (pinfunction "IO_L38N_A4_M1CLKN_1_H11") (pintype "bidirectional"))
    )
    (net (code "145") (name "/VME_D22") (class "Default")
      (node (ref "IC40") (pin "H13") (pinfunction "IO_L39P_M1A3_1_H13") (pintype "bidirectional"))
    )
    (net (code "146") (name "/VME_D23") (class "Default")
      (node (ref "IC40") (pin "H14") (pinfunction "IO_L39N_M1ODT_1_H14") (pintype "bidirectional"))
    )
    (net (code "147") (name "/VME_D24") (class "Default")
      (node (ref "IC40") (pin "J11") (pinfunction "IO_L40P_GCLK11_M1A5_1_J11") (pintype "bidirectional"))
    )
    (net (code "148") (name "/VME_D25") (class "Default")
      (node (ref "IC40") (pin "J12") (pinfunction "IO_L40N_GCLK10_M1A6_1_J12") (pintype "bidirectional"))
    )
    (net (code "149") (name "/VME_D26") (class "Default")
      (node (ref "IC40") (pin "J13") (pinfunction "IO_L41P_GCLK9_IRDY1_M1RASN_1_J13") (pintype "bidirectional"))
    )
    (net (code "150") (name "/VME_D27") (class "Default")
      (node (ref "IC40") (pin "K14") (pinfunction "IO_L41N_GCLK8_M1CASN_1_K14") (pintype "bidirectional"))
    )
    (net (code "151") (name "/VME_D28") (class "Default")
      (node (ref "IC40") (pin "K12") (pinfunction "IO_L42P_GCLK7_M1UDM_1_K12") (pintype "bidirectional"))
    )
    (net (code "152") (name "/VME_D29") (class "Default")
      (node (ref "IC40") (pin "K11") (pinfunction "IO_L42N_GCLK6_TRDY1_M1LDM_1_K11") (pintype "bidirectional"))
    )
    (net (code "153") (name "/VME_D30") (class "Default")
      (node (ref "IC40") (pin "J14") (pinfunction "IO_L43P_GCLK5_M1DQ4_1_J14") (pintype "bidirectional"))
    )
    (net (code "154") (name "/VME_D31") (class "Default")
      (node (ref "IC40") (pin "J16") (pinfunction "IO_L43N_GCLK4_M1DQ5_1_J16") (pintype "bidirectional"))
    )
    (net (code "155") (name "/VME_DS1") (class "Default")
      (node (ref "IC40") (pin "N16") (pinfunction "IO_L45N_A0_M1LDQSN_1_N16") (pintype "bidirectional"))
    )
    (net (code "156") (name "/VME_DS2") (class "Default")
      (node (ref "IC40") (pin "N14") (pinfunction "IO_L45P_A1_M1LDQS_1_N14") (pintype "bidirectional"))
    )
    (net (code "157") (name "/VME_DTACK") (class "Default")
      (node (ref "IC40") (pin "C2") (pinfunction "IO_L48N_M3BA1_3_C2") (pintype "bidirectional"))
    )
    (net (code "158") (name "/VME_DTACK_OE") (class "Default")
      (node (ref "IC40") (pin "C3") (pinfunction "IO_L48P_M3BA0_3_C3") (pintype "bidirectional"))
    )
    (net (code "160") (name "/VME_D_DIR") (class "Default")
      (node (ref "IC40") (pin "F4") (pinfunction "IO_L53P_M3CKE_3_F4") (pintype "bidirectional"))
    )
    (net (code "161") (name "/VME_D_OEN") (class "Default")
      (node (ref "IC40") (pin "F3") (pinfunction "IO_L53N_M3A12_3_F3") (pintype "bidirectional"))
    )
    (net (code "162") (name "/VME_GA0") (class "Default")
      (node (ref "IC40") (pin "R15") (pinfunction "IO_L49P_M1DQ10_1_R15") (pintype "bidirectional"))
    )
    (net (code "163") (name "/VME_GA1") (class "Default")
      (node (ref "IC40") (pin "R16") (pinfunction "IO_L49N_M1DQ11_1_R16") (pintype "bidirectional"))
    )
    (net (code "164") (name "/VME_GA2") (class "Default")
      (node (ref "IC40") (pin "R14") (pinfunction "IO_L50P_M1UDQS_1_R14") (pintype "bidirectional"))
    )
    (net (code "165") (name "/VME_GA3") (class "Default")
      (node (ref "IC40") (pin "T15") (pinfunction "IO_L50N_M1UDQSN_1_T15") (pintype "bidirectional"))
    )
    (net (code "166") (name "/VME_GA4") (class "Default")
      (node (ref "IC40") (pin "T14") (pinfunction "IO_L51P_M1DQ12_1_T14") (pintype "bidirectional"))
    )
    (net (code "167") (name "/VME_GAP") (class "Default")
      (node (ref "IC40") (pin "A3") (pinfunction "IO_L83N_VREF_3_A3") (pintype "bidirectional"))
    )
    (net (code "169") (name "/VME_IACK") (class "Default")
      (node (ref "IC40") (pin "E3") (pinfunction "IO_L54N_M3A11_3_E3") (pintype "bidirectional"))
    )
    (net (code "170") (name "/VME_IACKIN") (class "Default")
      (node (ref "IC40") (pin "F6") (pinfunction "IO_L55P_M3A13_3_F6") (pintype "bidirectional"))
    )
    (net (code "171") (name "/VME_IACKOUT") (class "Default")
      (node (ref "IC40") (pin "E4") (pinfunction "IO_L54P_M3RESET_3_E4") (pintype "bidirectional"))
    )
    (net (code "172") (name "/VME_IRQ1") (class "Default")
      (node (ref "IC40") (pin "T13") (pinfunction "IO_L51N_M1DQ13_1_T13") (pintype "bidirectional"))
    )
    (net (code "173") (name "/VME_IRQ2") (class "Default")
      (node (ref "IC40") (pin "R12") (pinfunction "IO_L52P_M1DQ14_1_R12") (pintype "bidirectional"))
    )
    (net (code "174") (name "/VME_IRQ3") (class "Default")
      (node (ref "IC40") (pin "T12") (pinfunction "IO_L52N_M1DQ15_1_T12") (pintype "bidirectional"))
    )
    (net (code "175") (name "/VME_IRQ4") (class "Default")
      (node (ref "IC40") (pin "L12") (pinfunction "IO_L53P_1_L12") (pintype "bidirectional"))
    )
    (net (code "176") (name "/VME_IRQ5") (class "Default")
      (node (ref "IC40") (pin "L13") (pinfunction "IO_L53N_VREF_1_L13") (pintype "bidirectional"))
    )
    (net (code "177") (name "/VME_IRQ6") (class "Default")
      (node (ref "IC40") (pin "M13") (pinfunction "IO_L74P_AWAKE_1_M13") (pintype "bidirectional"))
    )
    (net (code "178") (name "/VME_IRQ7") (class "Default")
      (node (ref "IC40") (pin "M14") (pinfunction "IO_L74N_DOUT_BUSY_1_M14") (pintype "bidirectional"))
    )
    (net (code "180") (name "/VME_LWORD") (class "Default")
      (node (ref "IC40") (pin "B3") (pinfunction "IO_L83P_3_B3") (pintype "bidirectional"))
    )
    (net (code "181") (name "/VME_RETRY") (class "Default")
      (node (ref "IC40") (pin "D1") (pinfunction "IO_L49N_M3A2_3_D1") (pintype "bidirectional"))
    )
    (net (code "182") (name "/VME_RETRY_OE") (class "Default")
      (node (ref "IC40") (pin "D3") (pinfunction "IO_L49P_M3A7_3_D3") (pintype "bidirectional"))
    )
    (net (code "183") (name "/VME_SYSCLK") (class "Default")
      (node (ref "IC40") (pin "G5") (pinfunction "IO_L51N_M3A4_3_G5") (pintype "bidirectional"))
    )
    (net (code "184") (name "/VME_SYSRESET") (class "Default")
      (node (ref "IC40") (pin "G6") (pinfunction "IO_L51P_M3A10_3_G6") (pintype "bidirectional"))
    )
    (net (code "185") (name "/VME_TCK") (class "Default")
      (node (ref "IC40") (pin "C11") (pinfunction "IO_L39P_0_C11") (pintype "bidirectional"))
    )
    (net (code "186") (name "/VME_TDI") (class "Default")
      (node (ref "IC40") (pin "C10") (pinfunction "IO_L37N_GCLK12_0_C10") (pintype "bidirectional"))
    )
    (net (code "187") (name "/VME_TDO") (class "Default")
      (node (ref "IC40") (pin "D8") (pinfunction "IO_L38P_0_D8") (pintype "bidirectional"))
    )
    (net (code "188") (name "/VME_TDO_OE") (class "Default")
      (node (ref "IC40") (pin "A11") (pinfunction "IO_L39N_0_A11") (pintype "bidirectional"))
    )
    (net (code "189") (name "/VME_TMS") (class "Default")
      (node (ref "IC40") (pin "C8") (pinfunction "IO_L38N_VREF_0_C8") (pintype "bidirectional"))
    )
    (net (code "190") (name "/VME_TRST") (class "Default")
      (node (ref "IC40") (pin "E10") (pinfunction "IO_L37P_GCLK13_0_E10") (pintype "bidirectional"))
    )
    (net (code "191") (name "/VME_WRITE") (class "Default")
      (node (ref "IC40") (pin "B1") (pinfunction "IO_L50N_M3BA2_3_B1") (pintype "bidirectional"))
    )
    (net (code "192") (name "GND") (class "Default")
      (node (ref "IC13") (pin "4") (pinfunction "GND_4") (pintype "power_in"))
      (node (ref "LD12") (pin "1") (pinfunction "C_1") (pintype "passive"))
      (node (ref "LD18") (pin "1") (pinfunction "C_1") (pintype "passive"))
      (node (ref "R132") (pin "1") (pinfunction "1_1") (pintype "passive"))
      (node (ref "R163") (pin "1") (pinfunction "1_1") (pintype "passive"))
      (node (ref "R167") (pin "1") (pinfunction "1_1") (pintype "passive"))
      (node (ref "R169") (pin "1") (pinfunction "1_1") (pintype "passive"))
      (node (ref "R32") (pin "1") (pinfunction "1_1") (pintype "passive"))
      (node (ref "R33") (pin "1") (pinfunction "1_1") (pintype "passive"))
      (node (ref "R35") (pin "1") (pinfunction "1_1") (pintype "passive"))
      (node (ref "R37") (pin "1") (pinfunction "1_1") (pintype "passive"))
      (node (ref "R38") (pin "1") (pinfunction "1_1") (pintype "passive"))
      (node (ref "SW1") (pin "10") (pinfunction "10_10") (pintype "passive"))
      (node (ref "SW1") (pin "11") (pinfunction "11_11") (pintype "passive"))
      (node (ref "SW1") (pin "12") (pinfunction "12_12") (pintype "passive"))
      (node (ref "SW1") (pin "13") (pinfunction "13_13") (pintype "passive"))
      (node (ref "SW1") (pin "14") (pinfunction "14_14") (pintype "passive"))
      (node (ref "SW1") (pin "15") (pinfunction "15_15") (pintype "passive"))
      (node (ref "SW1") (pin "16") (pinfunction "16_16") (pintype "passive"))
      (node (ref "SW1") (pin "9") (pinfunction "9_9") (pintype "passive"))
    )
    (net (code "193") (name "Net-(IC40A-IO_L1P_HSWAPEN_0)") (class "Default")
      (node (ref "IC40") (pin "C4") (pinfunction "IO_L1P_HSWAPEN_0_C4") (pintype "bidirectional"))
      (node (ref "R131") (pin "1") (pinfunction "1_1") (pintype "passive"))
      (node (ref "R132") (pin "2") (pinfunction "2_2") (pintype "passive"))
    )
    (net (code "194") (name "Net-(LD12-A)") (class "Default")
      (node (ref "LD12") (pin "2") (pinfunction "A_2") (pintype "passive"))
      (node (ref "R172") (pin "2") (pinfunction "2_2") (pintype "passive"))
    )
    (net (code "195") (name "Net-(LD18-A)") (class "Default")
      (node (ref "LD18") (pin "2") (pinfunction "A_2") (pintype "passive"))
      (node (ref "R173") (pin "2") (pinfunction "2_2") (pintype "passive"))
    )
    (net (code "196") (name "P3V3") (class "Default")
      (node (ref "IC13") (pin "8") (pinfunction "VDD_8") (pintype "power_in"))
      (node (ref "R131") (pin "2") (pinfunction "2_2") (pintype "passive"))
      (node (ref "R133") (pin "2") (pinfunction "2_2") (pintype "passive"))
      (node (ref "R136") (pin "2") (pinfunction "2_2") (pintype "passive"))
      (node (ref "R137") (pin "2") (pinfunction "2_2") (pintype "passive"))
      (node (ref "R139") (pin "2") (pinfunction "2_2") (pintype "passive"))
      (node (ref "R142") (pin "2") (pinfunction "2_2") (pintype "passive"))
      (node (ref "R143") (pin "2") (pinfunction "2_2") (pintype "passive"))
      (node (ref "R144") (pin "2") (pinfunction "2_2") (pintype "passive"))
      (node (ref "R147") (pin "2") (pinfunction "2_2") (pintype "passive"))
      (node (ref "R148") (pin "2") (pinfunction "2_2") (pintype "passive"))
      (node (ref "R149") (pin "2") (pinfunction "2_2") (pintype "passive"))
      (node (ref "R151") (pin "2") (pinfunction "2_2") (pintype "passive"))
      (node (ref "R153") (pin "2") (pinfunction "2_2") (pintype "passive"))
      (node (ref "R154") (pin "2") (pinfunction "2_2") (pintype "passive"))
      (node (ref "R159") (pin "2") (pinfunction "2_2") (pintype "passive"))
      (node (ref "R160") (pin "2") (pinfunction "2_2") (pintype "passive"))
      (node (ref "R161") (pin "2") (pinfunction "2_2") (pintype "passive"))
      (node (ref "R162") (pin "2") (pinfunction "2_2") (pintype "passive"))
      (node (ref "R207") (pin "2") (pinfunction "2_2") (pintype "passive"))
      (node (ref "R214") (pin "2") (pinfunction "2_2") (pintype "passive"))
      (node (ref "R215") (pin "2") (pinfunction "2_2") (pintype "passive"))
      (node (ref "R34") (pin "2") (pinfunction "2_2") (pintype "passive"))
    )
  )
)
